# esquema.net
KiCad netlist of a schematic drawn in Altium Designer
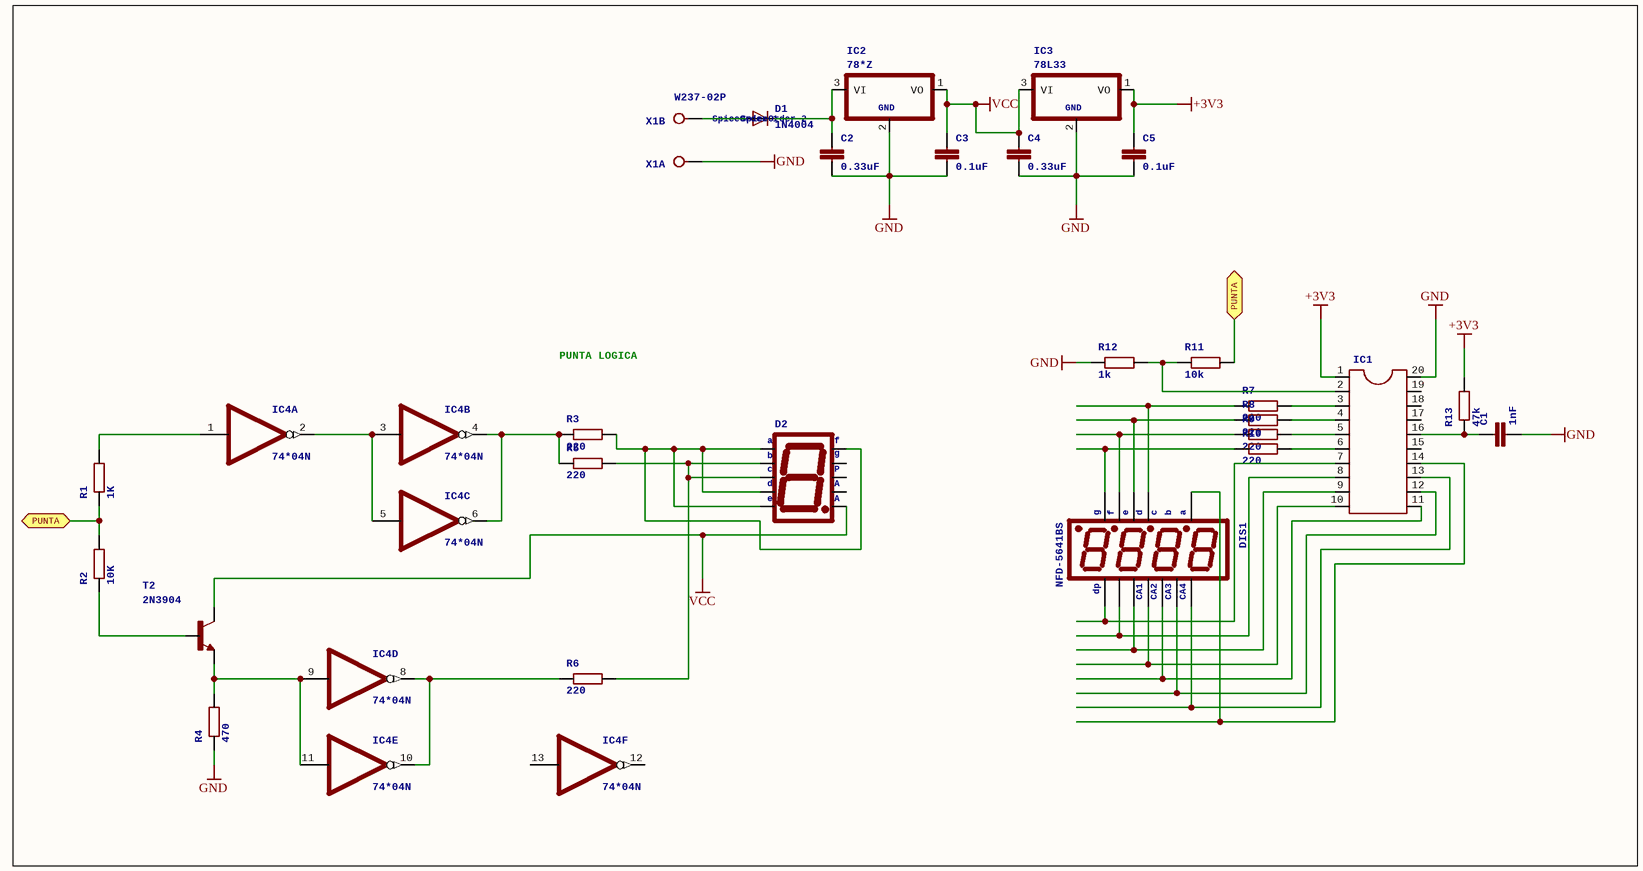
[diagram p0: esquema.SchDoc]

(export (version "E")
  (design (tool "Eeschema 10.0.6"))
  (components
    (comp (ref "C1")
      (value "1nF")
      (footprint "C050-024X044")
      (description "CAPACITOR, European symbol")
      (libsource (lib "") (part "C-EU050-024X044_1"))
    )
    (comp (ref "C2")
      (value "0.33uF")
      (footprint "C050-024X044")
      (description "CAPACITOR, European symbol")
      (libsource (lib "rcl") (part "C-EU050-024X044"))
    )
    (comp (ref "C3")
      (value "0.1uF")
      (footprint "C050-024X044")
      (description "CAPACITOR, European symbol")
      (libsource (lib "rcl") (part "C-EU050-024X044"))
    )
    (comp (ref "C4")
      (value "0.33uF")
      (footprint "C050-024X044")
      (description "CAPACITOR, European symbol")
      (libsource (lib "rcl") (part "C-EU050-024X044"))
    )
    (comp (ref "C5")
      (value "0.1uF")
      (footprint "C050-024X044")
      (description "CAPACITOR, European symbol")
      (libsource (lib "rcl") (part "C-EU050-024X044"))
    )
    (comp (ref "D1")
      (value "1N4004")
      (footprint "DO41-10")
      (description "DIODE   general purpose rectifier, 1 A")
      (fields (field (name "SPICEORDER1") "SpiceOrder 1") (field (name "SPICEORDER2") "SpiceOrder 2"))
      (libsource (lib "diode") (part "1N4004"))
    )
    (comp (ref "D2")
      (value "7SEG-CA")
      (footprint "7SEG-13")
      (description "7-segment DISPLAY   single anode, 13 mm")
      (fields
        (field (name "A") "a")
        (field (name "B") "b")
        (field (name "C") "c")
        (field (name "D") "d")
        (field (name "E") "e")
        (field (name "F") "f")
        (field (name "G") "g")
        (field (name "P") "P")
        (field (name "A_1") "A")
        (field (name "A_2") "A")
      )
      (libsource (lib "special") (part "7SEG-CA"))
    )
    (comp (ref "DIS1")
      (value "NFD-5641BS")
      (footprint "NFD-5641")
      (description "Four Digit 0.56\" CA Seven-Segment LED Display Futurlec part number: 7FR5641BS Created by RobG")
      (fields
        (field (name "CA3") "CA3")
        (field (name "CA4") "CA4")
        (field (name "DP") "dp")
        (field (name "A") "a")
        (field (name "B") "b")
        (field (name "C") "c")
        (field (name "D") "d")
        (field (name "E") "e")
        (field (name "F") "f")
        (field (name "G") "g")
        (field (name "CA1") "CA1")
        (field (name "CA2") "CA2")
      )
      (libsource (lib "display-nfd") (part "NFD-5641BS"))
    )
    (comp (ref "IC1")
      (value "DIL20S")
      (footprint "SOCKET-20")
      (description "Dual In Line / Socket")
      (libsource (lib "ic-package") (part "DIL20S"))
    )
    (comp (ref "IC2")
      (value "78*Z")
      (footprint "TO92")
      (fields (field (name "GND") "GND"))
      (libsource (lib "linear") (part "78*Z"))
    )
    (comp (ref "IC3")
      (value "78L33")
      (footprint "TO92")
      (fields (field (name "GND") "GND"))
      (libsource (lib "linear") (part "78*Z"))
    )
    (comp (ref "IC4")
      (value "74*04N")
      (footprint "DIL14")
      (description "Hex INVERTER")
      (libsource (lib "74xx-us") (part "74*04N"))
    )
    (comp (ref "R1")
      (value "1K")
      (footprint "0207/7")
      (description "RESISTOR, European symbol")
      (libsource (lib "rcl") (part "R-EU_0207/7"))
    )
    (comp (ref "R2")
      (value "10K")
      (footprint "0207/7")
      (description "RESISTOR, European symbol")
      (libsource (lib "rcl") (part "R-EU_0207/7"))
    )
    (comp (ref "R3")
      (value "220")
      (footprint "0207/7")
      (description "RESISTOR, European symbol")
      (libsource (lib "rcl") (part "R-EU_0207/7"))
    )
    (comp (ref "R4")
      (value "470")
      (footprint "0207/7")
      (description "RESISTOR, European symbol")
      (libsource (lib "rcl") (part "R-EU_0207/7"))
    )
    (comp (ref "R5")
      (value "220")
      (footprint "0207/7")
      (description "RESISTOR, European symbol")
      (libsource (lib "rcl") (part "R-EU_0207/7"))
    )
    (comp (ref "R6")
      (value "220")
      (footprint "0207/7")
      (description "RESISTOR, European symbol")
      (libsource (lib "rcl") (part "R-EU_0207/7"))
    )
    (comp (ref "R7")
      (value "220")
      (footprint "0207/7")
      (description "RESISTOR, European symbol")
      (libsource (lib "rcl") (part "R-EU_0207/7"))
    )
    (comp (ref "R8")
      (value "220")
      (footprint "0207/7")
      (description "RESISTOR, European symbol")
      (libsource (lib "rcl") (part "R-EU_0207/7"))
    )
    (comp (ref "R9")
      (value "220")
      (footprint "0207/7")
      (description "RESISTOR, European symbol")
      (libsource (lib "rcl") (part "R-EU_0207/7"))
    )
    (comp (ref "R10")
      (value "220")
      (footprint "0207/7")
      (description "RESISTOR, European symbol")
      (libsource (lib "rcl") (part "R-EU_0207/7"))
    )
    (comp (ref "R11")
      (value "10k")
      (footprint "0207/7")
      (description "RESISTOR, European symbol")
      (libsource (lib "rcl") (part "R-EU_0207/7"))
    )
    (comp (ref "R12")
      (value "1k")
      (footprint "0207/7")
      (description "RESISTOR, European symbol")
      (libsource (lib "rcl") (part "R-EU_0207/7"))
    )
    (comp (ref "R13")
      (value "47k")
      (footprint "0207/7")
      (description "RESISTOR, European symbol")
      (libsource (lib "rcl") (part "R-EU_0207/7"))
    )
    (comp (ref "T2")
      (value "2N3904")
      (footprint "TO92")
      (description "NPN TRANSISTOR")
      (libsource (lib "transistor") (part "2N3904"))
    )
    (comp (ref "X1")
      (value "W237-02P")
      (footprint "W237-132")
      (description "WAGO SREW CLAMP")
      (libsource (lib "con-wago-508") (part "W237-02P"))
    )
  )
  (nets
    (net (code "1") (name "+3V3") (class "Default")
      (node (ref "C5") (pin "1") (pinfunction "1_1") (pintype "passive"))
      (node (ref "IC1") (pin "1") (pinfunction "1_1") (pintype "passive"))
      (node (ref "IC3") (pin "1") (pinfunction "VO_1") (pintype "passive"))
      (node (ref "R13") (pin "2") (pinfunction "2_2") (pintype "passive"))
    )
    (net (code "2") (name "/PUNTA") (class "Default")
      (node (ref "R1") (pin "1") (pinfunction "1_1") (pintype "passive"))
      (node (ref "R11") (pin "2") (pinfunction "2_2") (pintype "passive"))
      (node (ref "R2") (pin "2") (pinfunction "2_2") (pintype "passive"))
    )
    (net (code "3") (name "GND") (class "Default")
      (node (ref "C1") (pin "2") (pinfunction "2_2") (pintype "passive"))
      (node (ref "C2") (pin "2") (pinfunction "2_2") (pintype "passive"))
      (node (ref "C3") (pin "2") (pinfunction "2_2") (pintype "passive"))
      (node (ref "C4") (pin "2") (pinfunction "2_2") (pintype "passive"))
      (node (ref "C5") (pin "2") (pinfunction "2_2") (pintype "passive"))
      (node (ref "IC1") (pin "20") (pinfunction "20_20") (pintype "passive"))
      (node (ref "IC2") (pin "2") (pinfunction "GND_2") (pintype "passive"))
      (node (ref "IC3") (pin "2") (pinfunction "GND_2") (pintype "passive"))
      (node (ref "R12") (pin "1") (pinfunction "1_1") (pintype "passive"))
      (node (ref "R4") (pin "1") (pinfunction "1_1") (pintype "passive"))
      (node (ref "X1") (pin "1") (pinfunction "KL_1") (pintype "passive"))
    )
    (net (code "4") (name "Net-(C1-Pad1)") (class "Default")
      (node (ref "C1") (pin "1") (pinfunction "1_1") (pintype "passive"))
      (node (ref "IC1") (pin "16") (pinfunction "16_16") (pintype "passive"))
      (node (ref "R13") (pin "1") (pinfunction "1_1") (pintype "passive"))
    )
    (net (code "5") (name "Net-(D2-A)") (class "Default")
      (node (ref "D2") (pin "1") (pinfunction "E_1") (pintype "passive"))
      (node (ref "D2") (pin "2") (pinfunction "D_2") (pintype "passive"))
      (node (ref "D2") (pin "7") (pinfunction "A_7") (pintype "passive"))
      (node (ref "D2") (pin "9") (pinfunction "F_9") (pintype "passive"))
      (node (ref "R3") (pin "2") (pinfunction "2_2") (pintype "passive"))
    )
    (net (code "6") (name "Net-(D2-B)") (class "Default")
      (node (ref "D2") (pin "4") (pinfunction "C_4") (pintype "passive"))
      (node (ref "D2") (pin "6") (pinfunction "B_6") (pintype "passive"))
      (node (ref "R5") (pin "2") (pinfunction "2_2") (pintype "passive"))
      (node (ref "R6") (pin "2") (pinfunction "2_2") (pintype "passive"))
    )
    (net (code "7") (name "Net-(DIS1-PadP$1)") (class "Default")
      (node (ref "DIS1") (pin "P$1") (pinfunction "P$1_P$1") (pintype "passive"))
      (node (ref "IC1") (pin "11") (pinfunction "11_11") (pintype "passive"))
    )
    (net (code "8") (name "Net-(DIS1-PadP$2)") (class "Default")
      (node (ref "DIS1") (pin "P$2") (pinfunction "P$2_P$2") (pintype "passive"))
      (node (ref "IC1") (pin "10") (pinfunction "10_10") (pintype "passive"))
    )
    (net (code "9") (name "Net-(DIS1-PadP$3)") (class "Default")
      (node (ref "DIS1") (pin "P$3") (pinfunction "P$3_P$3") (pintype "passive"))
      (node (ref "IC1") (pin "14") (pinfunction "14_14") (pintype "passive"))
    )
    (net (code "10") (name "Net-(DIS1-PadP$4)") (class "Default")
      (node (ref "DIS1") (pin "P$4") (pinfunction "P$4_P$4") (pintype "passive"))
      (node (ref "IC1") (pin "9") (pinfunction "9_9") (pintype "passive"))
    )
    (net (code "11") (name "Net-(DIS1-PadP$5)") (class "Default")
      (node (ref "DIS1") (pin "P$5") (pinfunction "P$5_P$5") (pintype "passive"))
      (node (ref "IC1") (pin "13") (pinfunction "13_13") (pintype "passive"))
    )
    (net (code "12") (name "Net-(DIS1-PadP$6)") (class "Default")
      (node (ref "DIS1") (pin "P$6") (pinfunction "P$6_P$6") (pintype "passive"))
      (node (ref "R10") (pin "1") (pinfunction "1_1") (pintype "passive"))
    )
    (net (code "13") (name "Net-(DIS1-PadP$7)") (class "Default")
      (node (ref "DIS1") (pin "P$7") (pinfunction "P$7_P$7") (pintype "passive"))
      (node (ref "IC1") (pin "8") (pinfunction "8_8") (pintype "passive"))
    )
    (net (code "14") (name "Net-(DIS1-PadP$8)") (class "Default")
      (node (ref "DIS1") (pin "P$8") (pinfunction "P$8_P$8") (pintype "passive"))
      (node (ref "R9") (pin "1") (pinfunction "1_1") (pintype "passive"))
    )
    (net (code "15") (name "Net-(DIS1-PadP$9)") (class "Default")
      (node (ref "DIS1") (pin "P$9") (pinfunction "P$9_P$9") (pintype "passive"))
      (node (ref "R8") (pin "1") (pinfunction "1_1") (pintype "passive"))
    )
    (net (code "16") (name "Net-(DIS1-PadP$10)") (class "Default")
      (node (ref "DIS1") (pin "P$10") (pinfunction "P$10_P$10") (pintype "passive"))
      (node (ref "IC1") (pin "12") (pinfunction "12_12") (pintype "passive"))
    )
    (net (code "17") (name "Net-(DIS1-PadP$11)") (class "Default")
      (node (ref "DIS1") (pin "P$11") (pinfunction "P$11_P$11") (pintype "passive"))
      (node (ref "IC1") (pin "7") (pinfunction "7_7") (pintype "passive"))
    )
    (net (code "18") (name "Net-(DIS1-PadP$12)") (class "Default")
      (node (ref "DIS1") (pin "P$12") (pinfunction "P$12_P$12") (pintype "passive"))
      (node (ref "R7") (pin "1") (pinfunction "1_1") (pintype "passive"))
    )
    (net (code "19") (name "Net-(IC1-Pad2)") (class "Default")
      (node (ref "IC1") (pin "2") (pinfunction "2_2") (pintype "passive"))
      (node (ref "R11") (pin "1") (pinfunction "1_1") (pintype "passive"))
      (node (ref "R12") (pin "2") (pinfunction "2_2") (pintype "passive"))
    )
    (net (code "20") (name "Net-(IC1-Pad3)") (class "Default")
      (node (ref "IC1") (pin "3") (pinfunction "3_3") (pintype "passive"))
      (node (ref "R7") (pin "2") (pinfunction "2_2") (pintype "passive"))
    )
    (net (code "21") (name "Net-(IC1-Pad4)") (class "Default")
      (node (ref "IC1") (pin "4") (pinfunction "4_4") (pintype "passive"))
      (node (ref "R8") (pin "2") (pinfunction "2_2") (pintype "passive"))
    )
    (net (code "22") (name "Net-(IC1-Pad5)") (class "Default")
      (node (ref "IC1") (pin "5") (pinfunction "5_5") (pintype "passive"))
      (node (ref "R9") (pin "2") (pinfunction "2_2") (pintype "passive"))
    )
    (net (code "23") (name "Net-(IC1-Pad6)") (class "Default")
      (node (ref "IC1") (pin "6") (pinfunction "6_6") (pintype "passive"))
      (node (ref "R10") (pin "2") (pinfunction "2_2") (pintype "passive"))
    )
    (net (code "24") (name "Net-(IC2-VI)") (class "Default")
      (node (ref "C2") (pin "1") (pinfunction "1_1") (pintype "passive"))
      (node (ref "D1") (pin "C") (pinfunction "C_C") (pintype "passive"))
      (node (ref "IC2") (pin "3") (pinfunction "VI_3") (pintype "passive"))
    )
    (net (code "25") (name "Net-(IC4A-I)") (class "Default")
      (node (ref "IC4") (pin "1") (pinfunction "I_1") (pintype "passive"))
      (node (ref "R1") (pin "2") (pinfunction "2_2") (pintype "passive"))
    )
    (net (code "26") (name "Net-(IC4A-O)") (class "Default")
      (node (ref "IC4") (pin "2") (pinfunction "O_2") (pintype "output"))
      (node (ref "IC4") (pin "3") (pinfunction "I_3") (pintype "passive"))
      (node (ref "IC4") (pin "5") (pinfunction "I_5") (pintype "passive"))
    )
    (net (code "27") (name "Net-(IC4B-O)") (class "Default")
      (node (ref "IC4") (pin "4") (pinfunction "O_4") (pintype "output"))
      (node (ref "IC4") (pin "6") (pinfunction "O_6") (pintype "output"))
      (node (ref "R3") (pin "1") (pinfunction "1_1") (pintype "passive"))
      (node (ref "R5") (pin "1") (pinfunction "1_1") (pintype "passive"))
    )
    (net (code "28") (name "Net-(IC4D-I)") (class "Default")
      (node (ref "IC4") (pin "11") (pinfunction "I_11") (pintype "passive"))
      (node (ref "IC4") (pin "9") (pinfunction "I_9") (pintype "passive"))
      (node (ref "R4") (pin "2") (pinfunction "2_2") (pintype "passive"))
      (node (ref "T2") (pin "3") (pinfunction "E_3") (pintype "passive"))
    )
    (net (code "29") (name "Net-(IC4D-O)") (class "Default")
      (node (ref "IC4") (pin "10") (pinfunction "O_10") (pintype "output"))
      (node (ref "IC4") (pin "8") (pinfunction "O_8") (pintype "output"))
      (node (ref "R6") (pin "1") (pinfunction "1_1") (pintype "passive"))
    )
    (net (code "30") (name "Net-(T2-B)") (class "Default")
      (node (ref "R2") (pin "1") (pinfunction "1_1") (pintype "passive"))
      (node (ref "T2") (pin "2") (pinfunction "B_2") (pintype "passive"))
    )
    (net (code "31") (name "Net-(X1B-KL)") (class "Default")
      (node (ref "D1") (pin "A") (pinfunction "A_A") (pintype "passive"))
      (node (ref "X1") (pin "2") (pinfunction "KL_2") (pintype "passive"))
    )
    (net (code "32") (name "VCC") (class "Default")
      (node (ref "C3") (pin "1") (pinfunction "1_1") (pintype "passive"))
      (node (ref "C4") (pin "1") (pinfunction "1_1") (pintype "passive"))
      (node (ref "D2") (pin "8") (pinfunction "CA2_8") (pintype "passive"))
      (node (ref "IC2") (pin "1") (pinfunction "VO_1") (pintype "passive"))
      (node (ref "IC3") (pin "3") (pinfunction "VI_3") (pintype "passive"))
      (node (ref "T2") (pin "1") (pinfunction "C_1") (pintype "passive"))
    )
    (net (code "33") (name "unconnected-(D2-CA1-Pad3)") (class "Default")
      (node (ref "D2") (pin "3") (pinfunction "CA1_3") (pintype "passive"))
    )
    (net (code "34") (name "unconnected-(D2-DP-Pad5)") (class "Default")
      (node (ref "D2") (pin "5") (pinfunction "DP_5") (pintype "passive"))
    )
    (net (code "35") (name "unconnected-(D2-G-Pad10)") (class "Default")
      (node (ref "D2") (pin "10") (pinfunction "G_10") (pintype "passive"))
    )
    (net (code "36") (name "unconnected-(IC1-Pad15)") (class "Default")
      (node (ref "IC1") (pin "15") (pinfunction "15_15") (pintype "passive"))
    )
    (net (code "37") (name "unconnected-(IC1-Pad17)") (class "Default")
      (node (ref "IC1") (pin "17") (pinfunction "17_17") (pintype "passive"))
    )
    (net (code "38") (name "unconnected-(IC1-Pad18)") (class "Default")
      (node (ref "IC1") (pin "18") (pinfunction "18_18") (pintype "passive"))
    )
    (net (code "39") (name "unconnected-(IC1-Pad19)") (class "Default")
      (node (ref "IC1") (pin "19") (pinfunction "19_19") (pintype "passive"))
    )
    (net (code "40") (name "unconnected-(IC4F-I-Pad13)") (class "Default")
      (node (ref "IC4") (pin "13") (pinfunction "I_13") (pintype "passive"))
    )
    (net (code "41") (name "unconnected-(IC4F-O-Pad12)") (class "Default")
      (node (ref "IC4") (pin "12") (pinfunction "O_12") (pintype "output"))
    )
  )
)
